# Peachy1-99-6-f.net
KiCad netlist of a schematic drawn in EAGLE
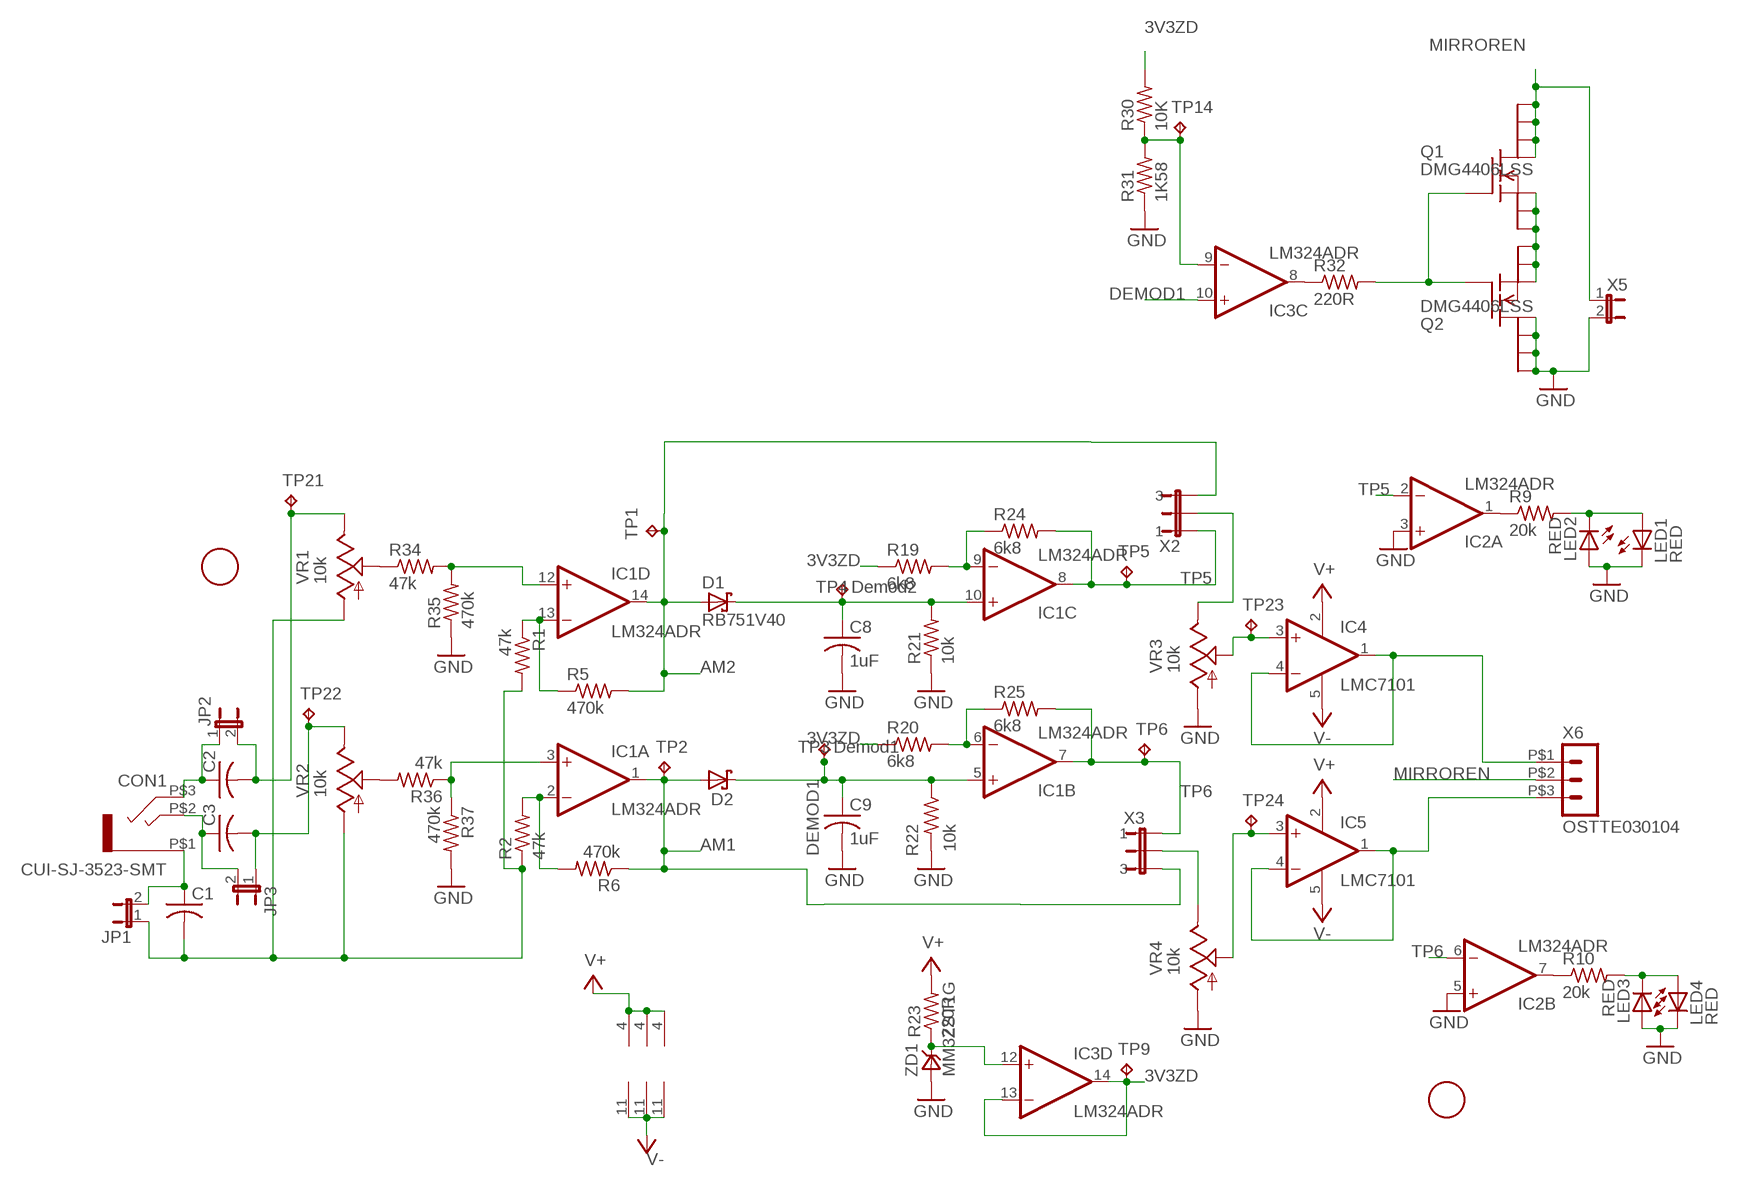
[diagram p0: schematic, sheet 1]
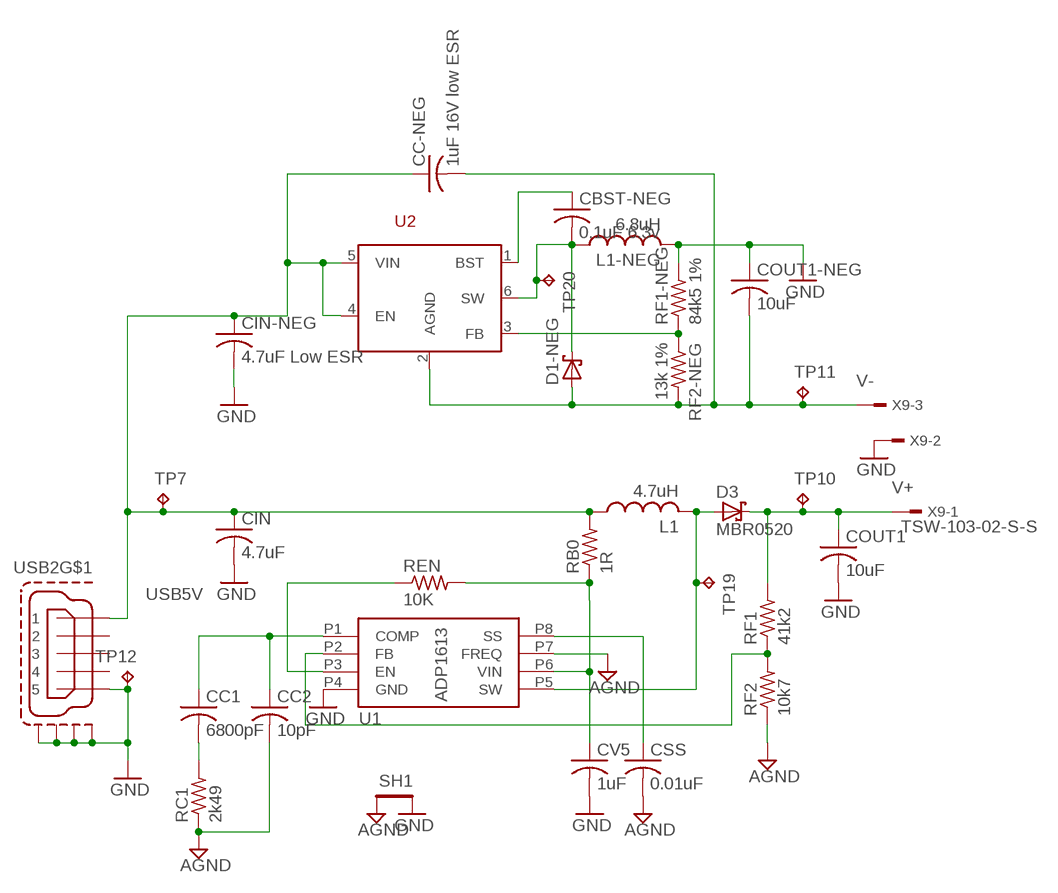
[diagram p1: schematic, sheet 2]
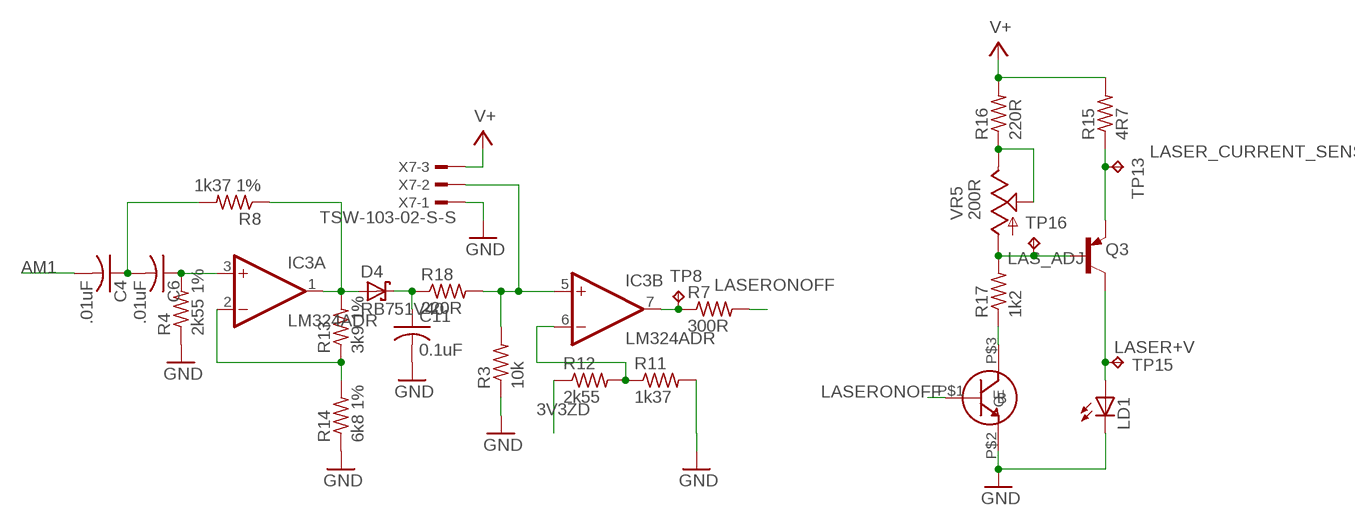
[diagram p2: schematic, sheet 3]
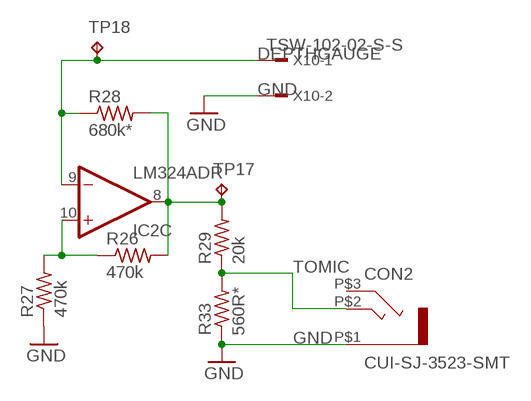
[diagram p3: schematic, sheet 4]

(export (version "E")
  (design (tool "Eeschema 10.0.6"))
  (components
    (comp (ref "CBST-NEG")
      (value "0.1uF 6.3v")
      (footprint "eagle-import:C0805")
      (fields (field (name "MPN") "CL21B104KACNNNC"))
      (libsource (lib "eagle-import") (part "C-US0805"))
    )
    (comp (ref "CC-NEG")
      (value "1uF 16V low ESR")
      (footprint "eagle-import:C0805")
      (fields (field (name "MPN") "CL21B105KBFNNNE"))
      (libsource (lib "eagle-import") (part "C-US0805"))
    )
    (comp (ref "CC1")
      (value "6800pF")
      (footprint "eagle-import:C0805")
      (fields (field (name "MPN") "CL21B682KBANNNC"))
      (libsource (lib "eagle-import") (part "C-US0805"))
    )
    (comp (ref "CC2")
      (value "10pF")
      (footprint "eagle-import:C0805")
      (fields (field (name "MPN") "CL21C100JCANNNC"))
      (libsource (lib "eagle-import") (part "C-US0805"))
    )
    (comp (ref "CIN")
      (value "4.7uF")
      (footprint "eagle-import:C0805")
      (fields (field (name "MPN") "CL21A475KOFNNNE"))
      (libsource (lib "eagle-import") (part "C-US0805"))
    )
    (comp (ref "CIN-NEG")
      (value "4.7uF Low ESR")
      (footprint "eagle-import:C0805")
      (fields (field (name "MPN") "CL21A475KOFNNNE"))
      (libsource (lib "eagle-import") (part "C-US0805"))
    )
    (comp (ref "COUT1")
      (value "10uF")
      (footprint "eagle-import:C0805")
      (fields (field (name "MPN") "CL21B106KQQNNNE"))
      (libsource (lib "eagle-import") (part "C-US0805"))
    )
    (comp (ref "COUT1-NEG")
      (value "10uF")
      (footprint "eagle-import:C0805")
      (fields (field (name "MPN") "CL21B106KQQNNNE"))
      (libsource (lib "eagle-import") (part "C-US0805"))
    )
    (comp (ref "CSS")
      (value "0.01uF")
      (footprint "eagle-import:C0805")
      (fields (field (name "MPN") "CL21B103KBANNNC"))
      (libsource (lib "eagle-import") (part "C-US0805"))
    )
    (comp (ref "CV5")
      (value "1uF")
      (footprint "eagle-import:C0805")
      (fields (field (name "MPN") "CL21B105KBFNNNE"))
      (libsource (lib "eagle-import") (part "C-US0805"))
    )
    (comp (ref "D1-NEG")
      (value "MBR0520LT1G")
      (footprint "eagle-import:SOD123")
      (fields (field (name "MPN") "MBR0520LT3G"))
      (libsource (lib "eagle-import") (part "SCHOTTKYSOD123"))
    )
    (comp (ref "D3")
      (value "MBR0520")
      (footprint "eagle-import:SOD123")
      (fields (field (name "MPN") "MBR0520LT3G"))
      (libsource (lib "eagle-import") (part "SCHOTTKYSOD123"))
    )
    (comp (ref "L1")
      (value "4.7uH")
      (footprint "eagle-import:L1210")
      (fields (field (name "MPN") "LQH32PN4R7NN0L"))
      (libsource (lib "eagle-import") (part "L-USL1210"))
    )
    (comp (ref "L1-NEG")
      (value "6.8uH")
      (footprint "eagle-import:L1210")
      (fields (field (name "MPN") "LQH32PN6R8NN0"))
      (libsource (lib "eagle-import") (part "L-USL1210"))
    )
    (comp (ref "RB0")
      (value "1R")
      (footprint "eagle-import:R0805")
      (fields (field (name "MPN") "RMCF0805JT1R00 "))
      (libsource (lib "eagle-import") (part "R-US_R0805"))
    )
    (comp (ref "RC1")
      (value "2k49")
      (footprint "eagle-import:R0805")
      (fields (field (name "MPN") "RMCF0805FT2K49"))
      (libsource (lib "eagle-import") (part "R-US_R0805"))
    )
    (comp (ref "REN")
      (value "10K")
      (footprint "eagle-import:R0805")
      (fields (field (name "MPN") "RMCF0805JT10K0"))
      (libsource (lib "eagle-import") (part "R-US_R0805"))
    )
    (comp (ref "RF1")
      (value "41k2")
      (footprint "eagle-import:R0805")
      (fields (field (name "MPN") "RC0805FR-0741K2L"))
      (libsource (lib "eagle-import") (part "R-US_R0805"))
    )
    (comp (ref "RF1-NEG")
      (value "84k5 1%")
      (footprint "eagle-import:R0805")
      (fields (field (name "MPN") "RC0805FR-0784K5L"))
      (libsource (lib "eagle-import") (part "R-US_R0805"))
    )
    (comp (ref "RF2")
      (value "10k7")
      (footprint "eagle-import:R0805")
      (fields (field (name "MPN") "RC2012F1072CS"))
      (libsource (lib "eagle-import") (part "R-US_R0805"))
    )
    (comp (ref "RF2-NEG")
      (value "13k 1%")
      (footprint "eagle-import:R0805")
      (fields (field (name "MPN") "RC0805FR-0713KL"))
      (libsource (lib "eagle-import") (part "R-US_R0805"))
    )
    (comp (ref "SH1")
      (value "SHORT-HT5")
      (footprint "eagle-import:SHORT_TOP-50")
      (libsource (lib "eagle-import") (part "SHORT-HT5"))
    )
    (comp (ref "TP7")
      (value "TP017HOLE")
      (footprint "eagle-import:TP017TH")
      (libsource (lib "eagle-import") (part "TP017HOLE"))
    )
    (comp (ref "TP10")
      (value "TP017HOLE")
      (footprint "eagle-import:TP017TH")
      (fields (field (name "TP_SIGNAL_NAME") "+V"))
      (libsource (lib "eagle-import") (part "TP017HOLE"))
    )
    (comp (ref "TP11")
      (value "TP017HOLE")
      (footprint "eagle-import:TP017TH")
      (fields (field (name "TP_SIGNAL_NAME") "V-"))
      (libsource (lib "eagle-import") (part "TP017HOLE"))
    )
    (comp (ref "TP12")
      (value "TP017HOLE")
      (footprint "eagle-import:TP017TH")
      (libsource (lib "eagle-import") (part "TP017HOLE"))
    )
    (comp (ref "TP19")
      (value "TP017HOLE")
      (footprint "eagle-import:TP017TH")
      (fields (field (name "TP_SIGNAL_NAME") "SW+"))
      (libsource (lib "eagle-import") (part "TP017HOLE"))
    )
    (comp (ref "TP20")
      (value "TP017HOLE")
      (footprint "eagle-import:TP017TH")
      (libsource (lib "eagle-import") (part "TP017HOLE"))
    )
    (comp (ref "U1")
      (value "ADP1613")
      (footprint "eagle-import:RM-8")
      (fields (field (name "MPN") "ADP1613ARMZ-R7"))
      (libsource (lib "eagle-import") (part "ADP1613"))
    )
    (comp (ref "U2")
      (value "ADP2300")
      (footprint "eagle-import:TSOT23-6")
      (fields (field (name "MPN") "ADP2300AUJZ-R7"))
      (libsource (lib "eagle-import") (part "ADP2300"))
    )
    (comp (ref "USB2")
      (value "FCI-MICROUSBAPCIRCUITS")
      (footprint "eagle-import:FCI-USB-10118193-APCIRCUITS")
      (fields (field (name "MPN") "10118193-0001LF"))
      (libsource (lib "eagle-import") (part "FCI-MICROUSBAPCIRCUITS"))
    )
    (comp (ref "X9")
      (value "TSW-103-02-S-S")
      (footprint "eagle-import:TSW-103-02-S-S")
      (fields (field (name "MPN") "TSW-103-07-T-S"))
      (libsource (lib "eagle-import") (part "TSW-103-02-S-S"))
    )
    (comp (ref "C4")
      (value ".01uF")
      (footprint "eagle-import:C0805")
      (fields (field (name "MPN") "CL21B103KBANNNC"))
      (libsource (lib "eagle-import") (part "C-US0805"))
    )
    (comp (ref "C6")
      (value ".01uF")
      (footprint "eagle-import:C0805")
      (fields (field (name "MPN") "CL21B103KBANNNC"))
      (libsource (lib "eagle-import") (part "C-US0805"))
    )
    (comp (ref "C11")
      (value "0.1uF")
      (footprint "eagle-import:C0805")
      (fields (field (name "MPN") "CL21B104KACNNNC"))
      (libsource (lib "eagle-import") (part "C-US0805"))
    )
    (comp (ref "D4")
      (value "RB751V40")
      (footprint "eagle-import:SOD323-R")
      (fields (field (name "MPN") "RB751V40,115"))
      (libsource (lib "eagle-import") (part "RB751V40"))
    )
    (comp (ref "IC3")
      (value "LM324ADR")
      (footprint "eagle-import:SOIC14(TI-PKG-D)")
      (fields (field (name "MPN") "LM324ADR"))
      (libsource (lib "eagle-import") (part "LM324ADR"))
    )
    (comp (ref "LD1")
      (value "LASERDIODELD2")
      (footprint "eagle-import:LASERDIODE2")
      (fields (field (name "MPN") "3 x (0552-2-15-15-11-27-10-0)"))
      (libsource (lib "eagle-import") (part "LASERDIODELD2"))
    )
    (comp (ref "Q3")
      (value "BC857CT")
      (footprint "eagle-import:SC-75")
      (fields (field (name "MPN") "BC857CT,115"))
      (libsource (lib "eagle-import") (part "BC857CT"))
    )
    (comp (ref "Q4")
      (value "MMBT3904")
      (footprint "eagle-import:SOT23")
      (fields (field (name "MPN") "MMBT3904,215"))
      (libsource (lib "eagle-import") (part "MMBT3904"))
    )
    (comp (ref "R3")
      (value "10k")
      (footprint "eagle-import:R0805")
      (fields (field (name "MPN") "RMCF0805JT10K0"))
      (libsource (lib "eagle-import") (part "R-US_R0805"))
    )
    (comp (ref "R4")
      (value "2k55 1%")
      (footprint "eagle-import:R0805")
      (fields (field (name "MPN") "RC0805FR-072K55L"))
      (libsource (lib "eagle-import") (part "R-US_R0805"))
    )
    (comp (ref "R7")
      (value "300R")
      (footprint "eagle-import:R0805")
      (fields (field (name "MPN") "RC0805JR-07300RL"))
      (libsource (lib "eagle-import") (part "R-US_R0805"))
    )
    (comp (ref "R8")
      (value "1k37 1%")
      (footprint "eagle-import:R0805")
      (fields (field (name "MPN") "RC0805FR-071K37L"))
      (libsource (lib "eagle-import") (part "R-US_R0805"))
    )
    (comp (ref "R11")
      (value "1k37")
      (footprint "eagle-import:R0805")
      (fields (field (name "MPN") "RC0805FR-071K37L"))
      (libsource (lib "eagle-import") (part "R-US_R0805"))
    )
    (comp (ref "R12")
      (value "2k55")
      (footprint "eagle-import:R0805")
      (fields (field (name "MPN") "RC0805FR-072K55L"))
      (libsource (lib "eagle-import") (part "R-US_R0805"))
    )
    (comp (ref "R13")
      (value "3k9 1%")
      (footprint "eagle-import:R0805")
      (fields (field (name "MPN") "RC0805FR-073K9L"))
      (libsource (lib "eagle-import") (part "R-US_R0805"))
    )
    (comp (ref "R14")
      (value "6k8 1%")
      (footprint "eagle-import:R0805")
      (fields (field (name "MPN") "RC0805FR-076K8L"))
      (libsource (lib "eagle-import") (part "R-US_R0805"))
    )
    (comp (ref "R15")
      (value "4R7")
      (footprint "eagle-import:R0805")
      (fields (field (name "MPN") "RMCF0805JT4R70"))
      (libsource (lib "eagle-import") (part "R-US_R0805"))
    )
    (comp (ref "R16")
      (value "220R")
      (footprint "eagle-import:R0805")
      (fields (field (name "MPN") "RC0805JR-07220RL"))
      (libsource (lib "eagle-import") (part "R-US_R0805"))
    )
    (comp (ref "R17")
      (value "1k2")
      (footprint "eagle-import:R0805")
      (fields (field (name "MPN") "RC2012J122CS"))
      (libsource (lib "eagle-import") (part "R-US_R0805"))
    )
    (comp (ref "R18")
      (value "220R")
      (footprint "eagle-import:R0805")
      (fields (field (name "MPN") "RMCF0805JT220R"))
      (libsource (lib "eagle-import") (part "R-US_R0805"))
    )
    (comp (ref "TP8")
      (value "TP017HOLE")
      (footprint "eagle-import:TP017TH")
      (libsource (lib "eagle-import") (part "TP017HOLE"))
    )
    (comp (ref "TP13")
      (value "TP017HOLE")
      (footprint "eagle-import:TP017TH")
      (fields (field (name "TP_SIGNAL_NAME") "LASER_CURRENT_SENSE"))
      (libsource (lib "eagle-import") (part "TP017HOLE"))
    )
    (comp (ref "TP15")
      (value "TP017HOLE")
      (footprint "eagle-import:TP017TH")
      (fields (field (name "TP_SIGNAL_NAME") "LASER+V"))
      (libsource (lib "eagle-import") (part "TP017HOLE"))
    )
    (comp (ref "TP16")
      (value "TP017HOLE")
      (footprint "eagle-import:TP017TH")
      (fields (field (name "TP_SIGNAL_NAME") "LAS_ADJ"))
      (libsource (lib "eagle-import") (part "TP017HOLE"))
    )
    (comp (ref "VR5")
      (value "200R")
      (footprint "eagle-import:TC33X")
      (fields (field (name "MPN") "???"))
      (libsource (lib "eagle-import") (part "TRIM_US-TC33X"))
    )
    (comp (ref "X7")
      (value "TSW-103-02-S-S")
      (footprint "eagle-import:TSW-103-02-S-S")
      (fields (field (name "MPN") "TSW-103-07-T-S"))
      (libsource (lib "eagle-import") (part "TSW-103-02-S-S"))
    )
    (comp (ref "C1")
      (value "C-US0805")
      (footprint "eagle-import:C0805")
      (libsource (lib "eagle-import") (part "C-US0805"))
    )
    (comp (ref "C2")
      (value "C-US0805")
      (footprint "eagle-import:C0805")
      (libsource (lib "eagle-import") (part "C-US0805"))
    )
    (comp (ref "C3")
      (value "C-US0805")
      (footprint "eagle-import:C0805")
      (libsource (lib "eagle-import") (part "C-US0805"))
    )
    (comp (ref "C8")
      (value "1uF")
      (footprint "eagle-import:C0805")
      (fields (field (name "MPN") "CL21B105KBFNNNE"))
      (libsource (lib "eagle-import") (part "C-US0805"))
    )
    (comp (ref "C9")
      (value "1uF")
      (footprint "eagle-import:C0805")
      (fields (field (name "MPN") "CL21B105KBFNNNE"))
      (libsource (lib "eagle-import") (part "C-US0805"))
    )
    (comp (ref "CON1")
      (value "CUI-SJ-3523-SMT")
      (footprint "eagle-import:CUI-SJ-3523-SMT")
      (fields (field (name "MPN") "SJ-3523-SMT-TR"))
      (libsource (lib "eagle-import") (part "CUI-SJ-3523-SMT"))
    )
    (comp (ref "D1")
      (value "RB751V40")
      (footprint "eagle-import:SOD323-R")
      (fields (field (name "MPN") "RB751V40,115"))
      (libsource (lib "eagle-import") (part "RB751V40"))
    )
    (comp (ref "D2")
      (value "RB751V40")
      (footprint "eagle-import:SOD323-R")
      (fields (field (name "MPN") "RB751V40,115"))
      (libsource (lib "eagle-import") (part "RB751V40"))
    )
    (comp (ref "IC1")
      (value "LM324ADR")
      (footprint "eagle-import:SOIC14(TI-PKG-D)")
      (fields (field (name "MPN") "LM324ADR"))
      (libsource (lib "eagle-import") (part "LM324ADR"))
    )
    (comp (ref "IC2")
      (value "LM324ADR")
      (footprint "eagle-import:SOIC14(TI-PKG-D)")
      (fields (field (name "MPN") "LM324ADR"))
      (libsource (lib "eagle-import") (part "LM324ADR"))
    )
    (comp (ref "IC4")
      (value "LMC7101")
      (footprint "eagle-import:SOT23-5")
      (fields (field (name "MPN") "LMC7101BYM5"))
      (libsource (lib "eagle-import") (part "LMC7101"))
    )
    (comp (ref "IC5")
      (value "LMC7101")
      (footprint "eagle-import:SOT23-5")
      (fields (field (name "MPN") "LMC7101BYM5"))
      (libsource (lib "eagle-import") (part "LMC7101"))
    )
    (comp (ref "JP1")
      (value "JUMPER-2SMD-NC")
      (footprint "eagle-import:SJ_2S")
      (libsource (lib "eagle-import") (part "JUMPER-2SMD-NC"))
    )
    (comp (ref "JP2")
      (value "JUMPER-2SMD-NC")
      (footprint "eagle-import:SJ_2S")
      (libsource (lib "eagle-import") (part "JUMPER-2SMD-NC"))
    )
    (comp (ref "JP3")
      (value "JUMPER-2SMD-NC")
      (footprint "eagle-import:SJ_2S")
      (libsource (lib "eagle-import") (part "JUMPER-2SMD-NC"))
    )
    (comp (ref "LED1")
      (value "RED")
      (footprint "eagle-import:CHIPLED_0603")
      (fields (field (name "MPN") "LS L29K-G1J2-1-Z"))
      (libsource (lib "eagle-import") (part "LEDCHIPLED_0603"))
    )
    (comp (ref "LED2")
      (value "RED")
      (footprint "eagle-import:CHIPLED_0603")
      (fields (field (name "MPN") "LS L29K-G1J2-1-Z"))
      (libsource (lib "eagle-import") (part "LEDCHIPLED_0603"))
    )
    (comp (ref "LED3")
      (value "RED")
      (footprint "eagle-import:CHIPLED_0603")
      (fields (field (name "MPN") "LS L29K-G1J2-1-Z"))
      (libsource (lib "eagle-import") (part "LEDCHIPLED_0603"))
    )
    (comp (ref "LED4")
      (value "RED")
      (footprint "eagle-import:CHIPLED_0603")
      (fields (field (name "MPN") "LS L29K-G1J2-1-Z"))
      (libsource (lib "eagle-import") (part "LEDCHIPLED_0603"))
    )
    (comp (ref "Q1")
      (value "DMG4406LSS")
      (footprint "eagle-import:SO8_DMG")
      (fields (field (name "MPN") "DMG4406LSS-13"))
      (libsource (lib "eagle-import") (part "DMG4406LSS"))
    )
    (comp (ref "Q2")
      (value "DMG4406LSS")
      (footprint "eagle-import:SO8_DMG")
      (fields (field (name "MPN") "DMG4406LSS-13"))
      (libsource (lib "eagle-import") (part "DMG4406LSS"))
    )
    (comp (ref "R1")
      (value "47k")
      (footprint "eagle-import:R0805")
      (fields (field (name "MPN") "RMCF0805JT47K0"))
      (libsource (lib "eagle-import") (part "R-US_R0805"))
    )
    (comp (ref "R2")
      (value "47k")
      (footprint "eagle-import:R0805")
      (fields (field (name "MPN") "RMCF0805JT47K0"))
      (libsource (lib "eagle-import") (part "R-US_R0805"))
    )
    (comp (ref "R5")
      (value "470k")
      (footprint "eagle-import:R0805")
      (fields (field (name "MPN") "RMCF0805JT470K"))
      (libsource (lib "eagle-import") (part "R-US_R0805"))
    )
    (comp (ref "R6")
      (value "470k")
      (footprint "eagle-import:R0805")
      (fields (field (name "MPN") "RMCF0805JT470K"))
      (libsource (lib "eagle-import") (part "R-US_R0805"))
    )
    (comp (ref "R9")
      (value "20k")
      (footprint "eagle-import:R0805")
      (fields (field (name "MPN") "RMCF0805JT20K0"))
      (libsource (lib "eagle-import") (part "R-US_R0805"))
    )
    (comp (ref "R10")
      (value "20k")
      (footprint "eagle-import:R0805")
      (fields (field (name "MPN") "RMCF0805JT20K0"))
      (libsource (lib "eagle-import") (part "R-US_R0805"))
    )
    (comp (ref "R19")
      (value "6k8")
      (footprint "eagle-import:R0805")
      (fields (field (name "MPN") "RC0805FR-076K8L"))
      (libsource (lib "eagle-import") (part "R-US_R0805"))
    )
    (comp (ref "R20")
      (value "6k8")
      (footprint "eagle-import:R0805")
      (fields (field (name "MPN") "RC0805FR-076K8L"))
      (libsource (lib "eagle-import") (part "R-US_R0805"))
    )
    (comp (ref "R21")
      (value "10k")
      (footprint "eagle-import:R0805")
      (fields (field (name "MPN") "RMCF0805JT10K0"))
      (libsource (lib "eagle-import") (part "R-US_R0805"))
    )
    (comp (ref "R22")
      (value "10k")
      (footprint "eagle-import:R0805")
      (fields (field (name "MPN") "RMCF0805JT10K0"))
      (libsource (lib "eagle-import") (part "R-US_R0805"))
    )
    (comp (ref "R23")
      (value "220R")
      (footprint "eagle-import:R0805")
      (fields (field (name "MPN") "RMCF0805JT220R"))
      (libsource (lib "eagle-import") (part "R-US_R0805"))
    )
    (comp (ref "R24")
      (value "6k8")
      (footprint "eagle-import:R0805")
      (fields (field (name "MPN") "RC0805FR-076K8L"))
      (libsource (lib "eagle-import") (part "R-US_R0805"))
    )
    (comp (ref "R25")
      (value "6k8")
      (footprint "eagle-import:R0805")
      (fields (field (name "MPN") "RC0805FR-076K8L"))
      (libsource (lib "eagle-import") (part "R-US_R0805"))
    )
    (comp (ref "R30")
      (value "10K")
      (footprint "eagle-import:R0805")
      (fields (field (name "MPN") "RMCF0805JT10K0"))
      (libsource (lib "eagle-import") (part "R-US_R0805"))
    )
    (comp (ref "R31")
      (value "1K58")
      (footprint "eagle-import:R0805")
      (fields (field (name "MPN") "RC0805FR-071K58L"))
      (libsource (lib "eagle-import") (part "R-US_R0805"))
    )
    (comp (ref "R32")
      (value "220R")
      (footprint "eagle-import:R0805")
      (fields (field (name "MPN") "RMCF0805JT220R"))
      (libsource (lib "eagle-import") (part "R-US_R0805"))
    )
    (comp (ref "R34")
      (value "47k")
      (footprint "eagle-import:R0805")
      (fields (field (name "MPN") "RMCF0805JT47K0"))
      (libsource (lib "eagle-import") (part "R-US_R0805"))
    )
    (comp (ref "R35")
      (value "470k")
      (footprint "eagle-import:R0805")
      (fields (field (name "MPN") "RMCF0805JT470K"))
      (libsource (lib "eagle-import") (part "R-US_R0805"))
    )
    (comp (ref "R36")
      (value "47k")
      (footprint "eagle-import:R0805")
      (fields (field (name "MPN") "RMCF0805JT47K0"))
      (libsource (lib "eagle-import") (part "R-US_R0805"))
    )
    (comp (ref "R37")
      (value "470k")
      (footprint "eagle-import:R0805")
      (fields (field (name "MPN") "RMCF0805JT470K"))
      (libsource (lib "eagle-import") (part "R-US_R0805"))
    )
    (comp (ref "TP1")
      (value "TP017HOLE")
      (footprint "eagle-import:TP017TH")
      (fields (field (name "TP_SIGNAL_NAME") "Preamp2"))
      (libsource (lib "eagle-import") (part "TP017HOLE"))
    )
    (comp (ref "TP2")
      (value "TP017HOLE")
      (footprint "eagle-import:TP017TH")
      (fields (field (name "TP_SIGNAL_NAME") "Preamp1"))
      (libsource (lib "eagle-import") (part "TP017HOLE"))
    )
    (comp (ref "TP3")
      (value "TP017HOLE")
      (footprint "eagle-import:TP017TH")
      (fields (field (name "TP_SIGNAL_NAME") "Demod1"))
      (libsource (lib "eagle-import") (part "TP017HOLE"))
    )
    (comp (ref "TP4")
      (value "TP017HOLE")
      (footprint "eagle-import:TP017TH")
      (fields (field (name "TP_SIGNAL_NAME") "Demod2"))
      (libsource (lib "eagle-import") (part "TP017HOLE"))
    )
    (comp (ref "TP5")
      (value "TP017HOLE")
      (footprint "eagle-import:TP017TH")
      (fields (field (name "TP_SIGNAL_NAME") "TP5"))
      (libsource (lib "eagle-import") (part "TP017HOLE"))
    )
    (comp (ref "TP6")
      (value "TP017HOLE")
      (footprint "eagle-import:TP017TH")
      (fields (field (name "TP_SIGNAL_NAME") "TP6"))
      (libsource (lib "eagle-import") (part "TP017HOLE"))
    )
    (comp (ref "TP9")
      (value "TP017HOLE")
      (footprint "eagle-import:TP017TH")
      (libsource (lib "eagle-import") (part "TP017HOLE"))
    )
    (comp (ref "TP14")
      (value "TP017HOLE")
      (footprint "eagle-import:TP017TH")
      (libsource (lib "eagle-import") (part "TP017HOLE"))
    )
    (comp (ref "TP21")
      (value "TP017HOLE")
      (footprint "eagle-import:TP017TH")
      (libsource (lib "eagle-import") (part "TP017HOLE"))
    )
    (comp (ref "TP22")
      (value "TP017HOLE")
      (footprint "eagle-import:TP017TH")
      (libsource (lib "eagle-import") (part "TP017HOLE"))
    )
    (comp (ref "TP23")
      (value "TP017HOLE")
      (footprint "eagle-import:TP017TH")
      (libsource (lib "eagle-import") (part "TP017HOLE"))
    )
    (comp (ref "TP24")
      (value "TP017HOLE")
      (footprint "eagle-import:TP017TH")
      (libsource (lib "eagle-import") (part "TP017HOLE"))
    )
    (comp (ref "U$2")
      (value "FIDUCIAL")
      (footprint "eagle-import:FIDUCIAL_1MM")
      (libsource (lib "eagle-import") (part "FIDUCIAL"))
    )
    (comp (ref "U$3")
      (value "FIDUCIAL")
      (footprint "eagle-import:FIDUCIAL_1MM")
      (libsource (lib "eagle-import") (part "FIDUCIAL"))
    )
    (comp (ref "VR1")
      (value "10k")
      (footprint "eagle-import:67W")
      (fields (field (name "MPN") "67WR10KLF"))
      (libsource (lib "eagle-import") (part "TRIM_US-67W"))
    )
    (comp (ref "VR2")
      (value "10k")
      (footprint "eagle-import:67W")
      (fields (field (name "MPN") "67WR10KLF"))
      (libsource (lib "eagle-import") (part "TRIM_US-67W"))
    )
    (comp (ref "VR3")
      (value "10k")
      (footprint "eagle-import:PVZ3A")
      (fields (field (name "MPN") "PVZ3A103C01R00"))
      (libsource (lib "eagle-import") (part "TRIM_US-PVZ3A"))
    )
    (comp (ref "VR4")
      (value "10k")
      (footprint "eagle-import:PVZ3A")
      (fields (field (name "MPN") "PVZ3A103C01R00"))
      (libsource (lib "eagle-import") (part "TRIM_US-PVZ3A"))
    )
    (comp (ref "X2")
      (value "JUMPER-31-2")
      (footprint "eagle-import:SJ_3_PASTE1&2")
      (libsource (lib "eagle-import") (part "JUMPER-31-2"))
    )
    (comp (ref "X3")
      (value "JUMPER-31-2")
      (footprint "eagle-import:SJ_3_PASTE1&2")
      (libsource (lib "eagle-import") (part "JUMPER-31-2"))
    )
    (comp (ref "X5")
      (value "JUMPER-2SMD-NO")
      (footprint "eagle-import:SJ_2S-NO")
      (libsource (lib "eagle-import") (part "JUMPER-2SMD-NO"))
    )
    (comp (ref "X6")
      (value "OSTTE030104")
      (footprint "eagle-import:OSTTE030104")
      (libsource (lib "eagle-import") (part "OSTTE030104"))
    )
    (comp (ref "ZD1")
      (value "MM3ZST1G")
      (footprint "eagle-import:SOD323-R")
      (fields (field (name "MPN") "BZX384-B3V3,115"))
      (libsource (lib "eagle-import") (part "MM3ZST1G"))
    )
    (comp (ref "CON2")
      (value "CUI-SJ-3523-SMT")
      (footprint "eagle-import:CUI-SJ-3523-SMT")
      (fields (field (name "MPN") "SJ-3523-SMT-TR"))
      (libsource (lib "eagle-import") (part "CUI-SJ-3523-SMT"))
    )
    (comp (ref "R26")
      (value "470k")
      (footprint "eagle-import:R0805")
      (fields (field (name "MPN") "RMCF0805JT470K"))
      (libsource (lib "eagle-import") (part "R-US_R0805"))
    )
    (comp (ref "R27")
      (value "470k")
      (footprint "eagle-import:R0805")
      (fields (field (name "MPN") "RMCF0805JT470K"))
      (libsource (lib "eagle-import") (part "R-US_R0805"))
    )
    (comp (ref "R28")
      (value "680k*")
      (footprint "eagle-import:70543-02")
      (fields (field (name "MPN") "PPTC021LFBN-RC"))
      (libsource (lib "eagle-import") (part "R-US_SOCKET(.1)"))
    )
    (comp (ref "R29")
      (value "20k")
      (footprint "eagle-import:R0805")
      (fields (field (name "MPN") "RMCF0805JT20K0"))
      (libsource (lib "eagle-import") (part "R-US_R0805"))
    )
    (comp (ref "R33")
      (value "560R*")
      (footprint "eagle-import:R0805")
      (fields (field (name "MPN") "RMCF0805JT560R"))
      (libsource (lib "eagle-import") (part "R-US_R0805"))
    )
    (comp (ref "TP17")
      (value "TP017HOLE")
      (footprint "eagle-import:TP017TH")
      (libsource (lib "eagle-import") (part "TP017HOLE"))
    )
    (comp (ref "TP18")
      (value "TP017HOLE")
      (footprint "eagle-import:TP017TH")
      (libsource (lib "eagle-import") (part "TP017HOLE"))
    )
    (comp (ref "X10")
      (value "TSW-102-02-S-S")
      (footprint "eagle-import:TSW-102-02-S-S")
      (libsource (lib "eagle-import") (part "TSW-102-02-S-S"))
    )
  )
  (nets
    (net (code "1") (name "3V3ZD") (class "Default")
      (node (ref "IC3") (pin "13") (pinfunction "-IN_13") (pintype "input"))
      (node (ref "IC3") (pin "14") (pinfunction "OUT_14") (pintype "output"))
      (node (ref "R12") (pin "1") (pinfunction "1_1") (pintype "passive"))
      (node (ref "R19") (pin "1") (pinfunction "1_1") (pintype "passive"))
      (node (ref "R20") (pin "1") (pinfunction "1_1") (pintype "passive"))
      (node (ref "R30") (pin "2") (pinfunction "2_2") (pintype "passive"))
      (node (ref "TP9") (pin "P$1") (pinfunction "TP_P$1") (pintype "input"))
    )
    (net (code "2") (name "AGND") (class "Default")
      (node (ref "CC2") (pin "2") (pinfunction "2_2") (pintype "passive"))
      (node (ref "CSS") (pin "2") (pinfunction "2_2") (pintype "passive"))
      (node (ref "RC1") (pin "1") (pinfunction "1_1") (pintype "passive"))
      (node (ref "RF2") (pin "1") (pinfunction "1_1") (pintype "passive"))
      (node (ref "SH1") (pin "1") (pinfunction "P$1_1") (pintype "bidirectional"))
      (node (ref "U1") (pin "P7") (pinfunction "FREQ_P7") (pintype "bidirectional"))
    )
    (net (code "3") (name "AM1") (class "Default")
      (node (ref "C4") (pin "2") (pinfunction "2_2") (pintype "passive"))
      (node (ref "D2") (pin "A") (pinfunction "A_A") (pintype "passive"))
      (node (ref "IC1") (pin "1") (pinfunction "OUT_1") (pintype "output"))
      (node (ref "R6") (pin "1") (pinfunction "1_1") (pintype "passive"))
      (node (ref "TP2") (pin "P$1") (pinfunction "TP_P$1") (pintype "input"))
      (node (ref "X3") (pin "3") (pinfunction "3_3") (pintype "passive"))
    )
    (net (code "4") (name "AM2") (class "Default")
      (node (ref "D1") (pin "A") (pinfunction "A_A") (pintype "passive"))
      (node (ref "IC1") (pin "14") (pinfunction "OUT_14") (pintype "output"))
      (node (ref "R5") (pin "2") (pinfunction "2_2") (pintype "passive"))
      (node (ref "TP1") (pin "P$1") (pinfunction "TP_P$1") (pintype "input"))
      (node (ref "X2") (pin "3") (pinfunction "3_3") (pintype "passive"))
    )
    (net (code "5") (name "DEMOD1") (class "Default")
      (node (ref "C9") (pin "1") (pinfunction "1_1") (pintype "passive"))
      (node (ref "D2") (pin "C") (pinfunction "C_C") (pintype "passive"))
      (node (ref "IC1") (pin "5") (pinfunction "+IN_5") (pintype "input"))
      (node (ref "IC3") (pin "10") (pinfunction "+IN_10") (pintype "input"))
      (node (ref "R22") (pin "1") (pinfunction "1_1") (pintype "passive"))
      (node (ref "TP3") (pin "P$1") (pinfunction "TP_P$1") (pintype "input"))
    )
    (net (code "6") (name "DEPTHGAUGE") (class "Default")
      (node (ref "IC2") (pin "9") (pinfunction "-IN_9") (pintype "input"))
      (node (ref "R28") (pin "1") (pinfunction "1_1") (pintype "passive"))
      (node (ref "TP18") (pin "P$1") (pinfunction "TP_P$1") (pintype "input"))
      (node (ref "X10") (pin "1") (pinfunction "1_1") (pintype "passive"))
    )
    (net (code "7") (name "GND") (class "Default")
      (node (ref "C11") (pin "2") (pinfunction "2_2") (pintype "passive"))
      (node (ref "C8") (pin "2") (pinfunction "2_2") (pintype "passive"))
      (node (ref "C9") (pin "2") (pinfunction "2_2") (pintype "passive"))
      (node (ref "CIN") (pin "2") (pinfunction "2_2") (pintype "passive"))
      (node (ref "CIN-NEG") (pin "2") (pinfunction "2_2") (pintype "passive"))
      (node (ref "CON2") (pin "P$1") (pinfunction "1_P$1") (pintype "passive"))
      (node (ref "COUT1") (pin "2") (pinfunction "2_2") (pintype "passive"))
      (node (ref "COUT1-NEG") (pin "1") (pinfunction "1_1") (pintype "passive"))
      (node (ref "CV5") (pin "2") (pinfunction "2_2") (pintype "passive"))
      (node (ref "IC2") (pin "3") (pinfunction "+IN_3") (pintype "input"))
      (node (ref "IC2") (pin "5") (pinfunction "+IN_5") (pintype "input"))
      (node (ref "L1-NEG") (pin "2") (pinfunction "2_2") (pintype "passive"))
      (node (ref "LD1") (pin "P$3") (pinfunction "C_P$3") (pintype "passive"))
      (node (ref "LED1") (pin "C") (pinfunction "C_C") (pintype "passive"))
      (node (ref "LED2") (pin "A") (pinfunction "A_A") (pintype "passive"))
      (node (ref "LED3") (pin "A") (pinfunction "A_A") (pintype "passive"))
      (node (ref "LED4") (pin "C") (pinfunction "C_C") (pintype "passive"))
      (node (ref "Q2") (pin "P$5") (pinfunction "D_P$5") (pintype "passive"))
      (node (ref "Q2") (pin "P$6") (pinfunction "D_P$6") (pintype "passive"))
      (node (ref "Q2") (pin "P$7") (pinfunction "D_P$7") (pintype "passive"))
      (node (ref "Q2") (pin "P$8") (pinfunction "D_P$8") (pintype "passive"))
      (node (ref "Q4") (pin "P$2") (pinfunction "E_P$2") (pintype "input"))
      (node (ref "R11") (pin "2") (pinfunction "2_2") (pintype "passive"))
      (node (ref "R14") (pin "1") (pinfunction "1_1") (pintype "passive"))
      (node (ref "R21") (pin "1") (pinfunction "1_1") (pintype "passive"))
      (node (ref "R22") (pin "2") (pinfunction "2_2") (pintype "passive"))
      (node (ref "R27") (pin "1") (pinfunction "1_1") (pintype "passive"))
      (node (ref "R3") (pin "1") (pinfunction "1_1") (pintype "passive"))
      (node (ref "R31") (pin "1") (pinfunction "1_1") (pintype "passive"))
      (node (ref "R33") (pin "1") (pinfunction "1_1") (pintype "passive"))
      (node (ref "R35") (pin "1") (pinfunction "1_1") (pintype "passive"))
      (node (ref "R37") (pin "2") (pinfunction "2_2") (pintype "passive"))
      (node (ref "R4") (pin "1") (pinfunction "1_1") (pintype "passive"))
      (node (ref "RF1-NEG") (pin "2") (pinfunction "2_2") (pintype "passive"))
      (node (ref "SH1") (pin "2") (pinfunction "P$2_2") (pintype "bidirectional"))
      (node (ref "TP12") (pin "P$1") (pinfunction "TP_P$1") (pintype "input"))
      (node (ref "U1") (pin "P4") (pinfunction "GND_P4") (pintype "bidirectional"))
      (node (ref "USB2") (pin "P$11") (pinfunction "S4_P$11") (pintype "passive"))
      (node (ref "USB2") (pin "P$5") (pinfunction "5_P$5") (pintype "input"))
      (node (ref "USB2") (pin "P$6") (pinfunction "S1_P$6") (pintype "passive"))
      (node (ref "USB2") (pin "P$7") (pinfunction "S2_P$7") (pintype "passive"))
      (node (ref "USB2") (pin "P$8") (pinfunction "S3_P$8") (pintype "passive"))
      (node (ref "VR3") (pin "P$1") (pinfunction "A_P$1") (pintype "passive"))
      (node (ref "VR4") (pin "P$1") (pinfunction "A_P$1") (pintype "passive"))
      (node (ref "X10") (pin "2") (pinfunction "1_2") (pintype "passive"))
      (node (ref "X5") (pin "2") (pinfunction "2_2") (pintype "passive"))
      (node (ref "X7") (pin "1") (pinfunction "1_1") (pintype "passive"))
      (node (ref "X9") (pin "2") (pinfunction "1_2") (pintype "passive"))
      (node (ref "ZD1") (pin "A") (pinfunction "A_A") (pintype "passive"))
    )
    (net (code "8") (name "LASERONOFF") (class "Default")
      (node (ref "Q4") (pin "P$1") (pinfunction "B_P$1") (pintype "input"))
      (node (ref "R7") (pin "2") (pinfunction "2_2") (pintype "passive"))
    )
    (net (code "9") (name "MIRROREN") (class "Default")
      (node (ref "Q1") (pin "P$5") (pinfunction "D_P$5") (pintype "passive"))
      (node (ref "Q1") (pin "P$6") (pinfunction "D_P$6") (pintype "passive"))
      (node (ref "Q1") (pin "P$7") (pinfunction "D_P$7") (pintype "passive"))
      (node (ref "Q1") (pin "P$8") (pinfunction "D_P$8") (pintype "passive"))
      (node (ref "X5") (pin "1") (pinfunction "1_1") (pintype "passive"))
      (node (ref "X6") (pin "P$2") (pinfunction "2_P$2") (pintype "passive"))
    )
    (net (code "10") (name "Net-(C1-Pad2)") (class "Default")
      (node (ref "C1") (pin "2") (pinfunction "2_2") (pintype "passive"))
      (node (ref "JP1") (pin "1") (pinfunction "1_1") (pintype "passive"))
      (node (ref "R1") (pin "2") (pinfunction "2_2") (pintype "passive"))
      (node (ref "R2") (pin "1") (pinfunction "1_1") (pintype "passive"))
      (node (ref "VR1") (pin "A") (pinfunction "A_A") (pintype "passive"))
      (node (ref "VR2") (pin "A") (pinfunction "A_A") (pintype "passive"))
    )
    (net (code "11") (name "Net-(C4-Pad1)") (class "Default")
      (node (ref "C4") (pin "1") (pinfunction "1_1") (pintype "passive"))
      (node (ref "C6") (pin "2") (pinfunction "2_2") (pintype "passive"))
      (node (ref "R8") (pin "2") (pinfunction "2_2") (pintype "passive"))
    )
    (net (code "12") (name "Net-(C11-Pad1)") (class "Default")
      (node (ref "C11") (pin "1") (pinfunction "1_1") (pintype "passive"))
      (node (ref "D4") (pin "C") (pinfunction "C_C") (pintype "passive"))
      (node (ref "R18") (pin "1") (pinfunction "1_1") (pintype "passive"))
    )
    (net (code "13") (name "Net-(CC1-Pad2)") (class "Default")
      (node (ref "CC1") (pin "2") (pinfunction "2_2") (pintype "passive"))
      (node (ref "RC1") (pin "2") (pinfunction "2_2") (pintype "passive"))
    )
    (net (code "14") (name "Net-(CON1-1)") (class "Default")
      (node (ref "C1") (pin "1") (pinfunction "1_1") (pintype "passive"))
      (node (ref "CON1") (pin "P$1") (pinfunction "1_P$1") (pintype "passive"))
      (node (ref "JP1") (pin "2") (pinfunction "2_2") (pintype "passive"))
    )
    (net (code "15") (name "Net-(CON1-2)") (class "Default")
      (node (ref "C2") (pin "1") (pinfunction "1_1") (pintype "passive"))
      (node (ref "CON1") (pin "P$3") (pinfunction "2_P$3") (pintype "passive"))
      (node (ref "JP2") (pin "1") (pinfunction "1_1") (pintype "passive"))
    )
    (net (code "16") (name "Net-(CON1-3)") (class "Default")
      (node (ref "C3") (pin "1") (pinfunction "1_1") (pintype "passive"))
      (node (ref "CON1") (pin "P$2") (pinfunction "3_P$2") (pintype "passive"))
      (node (ref "JP3") (pin "2") (pinfunction "2_2") (pintype "passive"))
    )
    (net (code "17") (name "Net-(IC1A-+IN)") (class "Default")
      (node (ref "IC1") (pin "3") (pinfunction "+IN_3") (pintype "input"))
      (node (ref "R36") (pin "1") (pinfunction "1_1") (pintype "passive"))
      (node (ref "R37") (pin "1") (pinfunction "1_1") (pintype "passive"))
    )
    (net (code "18") (name "Net-(IC1A--IN)") (class "Default")
      (node (ref "IC1") (pin "2") (pinfunction "-IN_2") (pintype "input"))
      (node (ref "R2") (pin "2") (pinfunction "2_2") (pintype "passive"))
      (node (ref "R6") (pin "2") (pinfunction "2_2") (pintype "passive"))
    )
    (net (code "19") (name "Net-(IC1B--IN)") (class "Default")
      (node (ref "IC1") (pin "6") (pinfunction "-IN_6") (pintype "input"))
      (node (ref "R20") (pin "2") (pinfunction "2_2") (pintype "passive"))
      (node (ref "R25") (pin "1") (pinfunction "1_1") (pintype "passive"))
    )
    (net (code "20") (name "Net-(IC1C-+IN)") (class "Default")
      (node (ref "C8") (pin "1") (pinfunction "1_1") (pintype "passive"))
      (node (ref "D1") (pin "C") (pinfunction "C_C") (pintype "passive"))
      (node (ref "IC1") (pin "10") (pinfunction "+IN_10") (pintype "input"))
      (node (ref "R21") (pin "2") (pinfunction "2_2") (pintype "passive"))
      (node (ref "TP4") (pin "P$1") (pinfunction "TP_P$1") (pintype "input"))
    )
    (net (code "21") (name "Net-(IC1C--IN)") (class "Default")
      (node (ref "IC1") (pin "9") (pinfunction "-IN_9") (pintype "input"))
      (node (ref "R19") (pin "2") (pinfunction "2_2") (pintype "passive"))
      (node (ref "R24") (pin "1") (pinfunction "1_1") (pintype "passive"))
    )
    (net (code "22") (name "Net-(IC1D-+IN)") (class "Default")
      (node (ref "IC1") (pin "12") (pinfunction "+IN_12") (pintype "input"))
      (node (ref "R34") (pin "2") (pinfunction "2_2") (pintype "passive"))
      (node (ref "R35") (pin "2") (pinfunction "2_2") (pintype "passive"))
    )
    (net (code "23") (name "Net-(IC1D--IN)") (class "Default")
      (node (ref "IC1") (pin "13") (pinfunction "-IN_13") (pintype "input"))
      (node (ref "R1") (pin "1") (pinfunction "1_1") (pintype "passive"))
      (node (ref "R5") (pin "1") (pinfunction "1_1") (pintype "passive"))
    )
    (net (code "24") (name "Net-(IC2A-OUT)") (class "Default")
      (node (ref "IC2") (pin "1") (pinfunction "OUT_1") (pintype "output"))
      (node (ref "R9") (pin "1") (pinfunction "1_1") (pintype "passive"))
    )
    (net (code "25") (name "Net-(IC2B-OUT)") (class "Default")
      (node (ref "IC2") (pin "7") (pinfunction "OUT_7") (pintype "output"))
      (node (ref "R10") (pin "1") (pinfunction "1_1") (pintype "passive"))
    )
    (net (code "26") (name "Net-(IC2C-+IN)") (class "Default")
      (node (ref "IC2") (pin "10") (pinfunction "+IN_10") (pintype "input"))
      (node (ref "R26") (pin "1") (pinfunction "1_1") (pintype "passive"))
      (node (ref "R27") (pin "2") (pinfunction "2_2") (pintype "passive"))
    )
    (net (code "27") (name "Net-(IC2C-OUT)") (class "Default")
      (node (ref "IC2") (pin "8") (pinfunction "OUT_8") (pintype "output"))
      (node (ref "R26") (pin "2") (pinfunction "2_2") (pintype "passive"))
      (node (ref "R28") (pin "2") (pinfunction "2_2") (pintype "passive"))
      (node (ref "R29") (pin "2") (pinfunction "2_2") (pintype "passive"))
      (node (ref "TP17") (pin "P$1") (pinfunction "TP_P$1") (pintype "input"))
    )
    (net (code "28") (name "Net-(IC3A-+IN)") (class "Default")
      (node (ref "C6") (pin "1") (pinfunction "1_1") (pintype "passive"))
      (node (ref "IC3") (pin "3") (pinfunction "+IN_3") (pintype "input"))
      (node (ref "R4") (pin "2") (pinfunction "2_2") (pintype "passive"))
    )
    (net (code "29") (name "Net-(IC3A--IN)") (class "Default")
      (node (ref "IC3") (pin "2") (pinfunction "-IN_2") (pintype "input"))
      (node (ref "R13") (pin "1") (pinfunction "1_1") (pintype "passive"))
      (node (ref "R14") (pin "2") (pinfunction "2_2") (pintype "passive"))
    )
    (net (code "30") (name "Net-(IC3A-OUT)") (class "Default")
      (node (ref "D4") (pin "A") (pinfunction "A_A") (pintype "passive"))
      (node (ref "IC3") (pin "1") (pinfunction "OUT_1") (pintype "output"))
      (node (ref "R13") (pin "2") (pinfunction "2_2") (pintype "passive"))
      (node (ref "R8") (pin "1") (pinfunction "1_1") (pintype "passive"))
    )
    (net (code "31") (name "Net-(IC3B-+IN)") (class "Default")
      (node (ref "IC3") (pin "5") (pinfunction "+IN_5") (pintype "input"))
      (node (ref "R18") (pin "2") (pinfunction "2_2") (pintype "passive"))
      (node (ref "R3") (pin "2") (pinfunction "2_2") (pintype "passive"))
      (node (ref "X7") (pin "2") (pinfunction "1_2") (pintype "passive"))
    )
    (net (code "32") (name "Net-(IC3B--IN)") (class "Default")
      (node (ref "IC3") (pin "6") (pinfunction "-IN_6") (pintype "input"))
      (node (ref "R11") (pin "1") (pinfunction "1_1") (pintype "passive"))
      (node (ref "R12") (pin "2") (pinfunction "2_2") (pintype "passive"))
    )
    (net (code "33") (name "Net-(IC3B-OUT)") (class "Default")
      (node (ref "IC3") (pin "7") (pinfunction "OUT_7") (pintype "output"))
      (node (ref "R7") (pin "1") (pinfunction "1_1") (pintype "passive"))
      (node (ref "TP8") (pin "P$1") (pinfunction "TP_P$1") (pintype "input"))
    )
    (net (code "34") (name "Net-(IC3C--IN)") (class "Default")
      (node (ref "IC3") (pin "9") (pinfunction "-IN_9") (pintype "input"))
      (node (ref "R30") (pin "1") (pinfunction "1_1") (pintype "passive"))
      (node (ref "R31") (pin "2") (pinfunction "2_2") (pintype "passive"))
      (node (ref "TP14") (pin "P$1") (pinfunction "TP_P$1") (pintype "input"))
    )
    (net (code "35") (name "Net-(IC3C-OUT)") (class "Default")
      (node (ref "IC3") (pin "8") (pinfunction "OUT_8") (pintype "output"))
      (node (ref "R32") (pin "1") (pinfunction "1_1") (pintype "passive"))
    )
    (net (code "36") (name "Net-(IC3D-+IN)") (class "Default")
      (node (ref "IC3") (pin "12") (pinfunction "+IN_12") (pintype "input"))
      (node (ref "R23") (pin "1") (pinfunction "1_1") (pintype "passive"))
      (node (ref "ZD1") (pin "C") (pinfunction "C_C") (pintype "passive"))
    )
    (net (code "37") (name "Net-(IC4-+IN)") (class "Default")
      (node (ref "IC4") (pin "3") (pinfunction "+IN_3") (pintype "input"))
      (node (ref "TP23") (pin "P$1") (pinfunction "TP_P$1") (pintype "input"))
      (node (ref "VR3") (pin "P$2") (pinfunction "S_P$2") (pintype "passive"))
    )
    (net (code "38") (name "Net-(IC4--IN)") (class "Default")
      (node (ref "IC4") (pin "1") (pinfunction "OUT_1") (pintype "output"))
      (node (ref "IC4") (pin "4") (pinfunction "-IN_4") (pintype "input"))
      (node (ref "X6") (pin "P$1") (pinfunction "1_P$1") (pintype "passive"))
    )
    (net (code "39") (name "Net-(IC5-+IN)") (class "Default")
      (node (ref "IC5") (pin "3") (pinfunction "+IN_3") (pintype "input"))
      (node (ref "TP24") (pin "P$1") (pinfunction "TP_P$1") (pintype "input"))
      (node (ref "VR4") (pin "P$2") (pinfunction "S_P$2") (pintype "passive"))
    )
    (net (code "40") (name "Net-(IC5--IN)") (class "Default")
      (node (ref "IC5") (pin "1") (pinfunction "OUT_1") (pintype "output"))
      (node (ref "IC5") (pin "4") (pinfunction "-IN_4") (pintype "input"))
      (node (ref "X6") (pin "P$3") (pinfunction "3_P$3") (pintype "passive"))
    )
    (net (code "41") (name "Net-(LD1-A)") (class "Default")
      (node (ref "LD1") (pin "P$1") (pinfunction "A_P$1") (pintype "passive"))
      (node (ref "Q3") (pin "P$3") (pinfunction "C_P$3") (pintype "passive"))
      (node (ref "TP15") (pin "P$1") (pinfunction "TP_P$1") (pintype "input"))
    )
    (net (code "42") (name "Net-(LED1-PadA)") (class "Default")
      (node (ref "LED1") (pin "A") (pinfunction "A_A") (pintype "passive"))
      (node (ref "LED2") (pin "C") (pinfunction "C_C") (pintype "passive"))
      (node (ref "R9") (pin "2") (pinfunction "2_2") (pintype "passive"))
    )
    (net (code "43") (name "Net-(LED3-PadC)") (class "Default")
      (node (ref "LED3") (pin "C") (pinfunction "C_C") (pintype "passive"))
      (node (ref "LED4") (pin "A") (pinfunction "A_A") (pintype "passive"))
      (node (ref "R10") (pin "2") (pinfunction "2_2") (pintype "passive"))
    )
    (net (code "44") (name "Net-(Q1-G)") (class "Default")
      (node (ref "Q1") (pin "P$4") (pinfunction "G_P$4") (pintype "passive"))
      (node (ref "Q2") (pin "P$4") (pinfunction "G_P$4") (pintype "passive"))
      (node (ref "R32") (pin "2") (pinfunction "2_2") (pintype "passive"))
    )
    (net (code "45") (name "Net-(Q1-S-PadP$1)") (class "Default")
      (node (ref "Q1") (pin "P$1") (pinfunction "S_P$1") (pintype "passive"))
      (node (ref "Q1") (pin "P$2") (pinfunction "S_P$2") (pintype "passive"))
      (node (ref "Q1") (pin "P$3") (pinfunction "S_P$3") (pintype "passive"))
      (node (ref "Q2") (pin "P$1") (pinfunction "S_P$1") (pintype "passive"))
      (node (ref "Q2") (pin "P$2") (pinfunction "S_P$2") (pintype "passive"))
      (node (ref "Q2") (pin "P$3") (pinfunction "S_P$3") (pintype "passive"))
    )
    (net (code "46") (name "Net-(Q3-B)") (class "Default")
      (node (ref "Q3") (pin "P$1") (pinfunction "B_P$1") (pintype "passive"))
      (node (ref "R17") (pin "2") (pinfunction "2_2") (pintype "passive"))
      (node (ref "TP16") (pin "P$1") (pinfunction "TP_P$1") (pintype "input"))
      (node (ref "VR5") (pin "P$1") (pinfunction "A_P$1") (pintype "passive"))
    )
    (net (code "47") (name "Net-(Q3-E)") (class "Default")
      (node (ref "Q3") (pin "P$2") (pinfunction "E_P$2") (pintype "passive"))
      (node (ref "R15") (pin "1") (pinfunction "1_1") (pintype "passive"))
      (node (ref "TP13") (pin "P$1") (pinfunction "TP_P$1") (pintype "input"))
    )
    (net (code "48") (name "Net-(Q4-C)") (class "Default")
      (node (ref "Q4") (pin "P$3") (pinfunction "C_P$3") (pintype "input"))
      (node (ref "R17") (pin "1") (pinfunction "1_1") (pintype "passive"))
    )
    (net (code "49") (name "Net-(R34-Pad1)") (class "Default")
      (node (ref "R34") (pin "1") (pinfunction "1_1") (pintype "passive"))
      (node (ref "VR1") (pin "S") (pinfunction "S_S") (pintype "passive"))
    )
    (net (code "50") (name "Net-(R36-Pad2)") (class "Default")
      (node (ref "R36") (pin "2") (pinfunction "2_2") (pintype "passive"))
      (node (ref "VR2") (pin "S") (pinfunction "S_S") (pintype "passive"))
    )
    (net (code "51") (name "Net-(TP19-TP)") (class "Default")
      (node (ref "D3") (pin "A") (pinfunction "A_A") (pintype "passive"))
      (node (ref "L1") (pin "2") (pinfunction "2_2") (pintype "passive"))
      (node (ref "TP19") (pin "P$1") (pinfunction "TP_P$1") (pintype "input"))
      (node (ref "U1") (pin "P5") (pinfunction "SW_P5") (pintype "bidirectional"))
    )
    (net (code "52") (name "Net-(TP20-TP)") (class "Default")
      (node (ref "CBST-NEG") (pin "2") (pinfunction "2_2") (pintype "passive"))
      (node (ref "D1-NEG") (pin "C") (pinfunction "C_C") (pintype "passive"))
      (node (ref "L1-NEG") (pin "1") (pinfunction "1_1") (pintype "passive"))
      (node (ref "TP20") (pin "P$1") (pinfunction "TP_P$1") (pintype "input"))
      (node (ref "U2") (pin "6") (pinfunction "SW_6") (pintype "bidirectional"))
    )
    (net (code "53") (name "Net-(TP21-TP)") (class "Default")
      (node (ref "C2") (pin "2") (pinfunction "2_2") (pintype "passive"))
      (node (ref "JP2") (pin "2") (pinfunction "2_2") (pintype "passive"))
      (node (ref "TP21") (pin "P$1") (pinfunction "TP_P$1") (pintype "input"))
      (node (ref "VR1") (pin "E") (pinfunction "E_E") (pintype "passive"))
    )
    (net (code "54") (name "Net-(TP22-TP)") (class "Default")
      (node (ref "C3") (pin "2") (pinfunction "2_2") (pintype "passive"))
      (node (ref "JP3") (pin "1") (pinfunction "1_1") (pintype "passive"))
      (node (ref "TP22") (pin "P$1") (pinfunction "TP_P$1") (pintype "input"))
      (node (ref "VR2") (pin "E") (pinfunction "E_E") (pintype "passive"))
    )
    (net (code "55") (name "Net-(U1-COMP)") (class "Default")
      (node (ref "CC1") (pin "1") (pinfunction "1_1") (pintype "passive"))
      (node (ref "CC2") (pin "1") (pinfunction "1_1") (pintype "passive"))
      (node (ref "U1") (pin "P1") (pinfunction "COMP_P1") (pintype "bidirectional"))
    )
    (net (code "56") (name "Net-(U1-EN)") (class "Default")
      (node (ref "REN") (pin "1") (pinfunction "1_1") (pintype "passive"))
      (node (ref "U1") (pin "P3") (pinfunction "EN_P3") (pintype "bidirectional"))
    )
    (net (code "57") (name "Net-(U1-FB)") (class "Default")
      (node (ref "RF1") (pin "1") (pinfunction "1_1") (pintype "passive"))
      (node (ref "RF2") (pin "2") (pinfunction "2_2") (pintype "passive"))
      (node (ref "U1") (pin "P2") (pinfunction "FB_P2") (pintype "bidirectional"))
    )
    (net (code "58") (name "Net-(U1-SS)") (class "Default")
      (node (ref "CSS") (pin "1") (pinfunction "1_1") (pintype "passive"))
      (node (ref "U1") (pin "P8") (pinfunction "SS_P8") (pintype "bidirectional"))
    )
    (net (code "59") (name "Net-(U1-VIN)") (class "Default")
      (node (ref "CV5") (pin "1") (pinfunction "1_1") (pintype "passive"))
      (node (ref "RB0") (pin "1") (pinfunction "1_1") (pintype "passive"))
      (node (ref "REN") (pin "2") (pinfunction "2_2") (pintype "passive"))
      (node (ref "U1") (pin "P6") (pinfunction "VIN_P6") (pintype "bidirectional"))
    )
    (net (code "60") (name "Net-(U2-BST)") (class "Default")
      (node (ref "CBST-NEG") (pin "1") (pinfunction "1_1") (pintype "passive"))
      (node (ref "U2") (pin "1") (pinfunction "BST_1") (pintype "bidirectional"))
    )
    (net (code "61") (name "Net-(U2-FB)") (class "Default")
      (node (ref "RF1-NEG") (pin "1") (pinfunction "1_1") (pintype "passive"))
      (node (ref "RF2-NEG") (pin "1") (pinfunction "1_1") (pintype "passive"))
      (node (ref "U2") (pin "3") (pinfunction "FB_3") (pintype "input"))
    )
    (net (code "62") (name "Net-(VR3-E)") (class "Default")
      (node (ref "VR3") (pin "P$3") (pinfunction "E_P$3") (pintype "passive"))
      (node (ref "X2") (pin "2") (pinfunction "2_2") (pintype "passive"))
    )
    (net (code "63") (name "Net-(VR4-E)") (class "Default")
      (node (ref "VR4") (pin "P$3") (pinfunction "E_P$3") (pintype "passive"))
      (node (ref "X3") (pin "2") (pinfunction "2_2") (pintype "passive"))
    )
    (net (code "64") (name "Net-(VR5-E)") (class "Default")
      (node (ref "R16") (pin "1") (pinfunction "1_1") (pintype "passive"))
      (node (ref "VR5") (pin "P$2") (pinfunction "S_P$2") (pintype "passive"))
      (node (ref "VR5") (pin "P$3") (pinfunction "E_P$3") (pintype "passive"))
    )
    (net (code "65") (name "TOMIC") (class "Default")
      (node (ref "CON2") (pin "P$2") (pinfunction "3_P$2") (pintype "passive"))
      (node (ref "R29") (pin "1") (pinfunction "1_1") (pintype "passive"))
      (node (ref "R33") (pin "2") (pinfunction "2_2") (pintype "passive"))
    )
    (net (code "66") (name "TP5") (class "Default")
      (node (ref "IC1") (pin "8") (pinfunction "OUT_8") (pintype "output"))
      (node (ref "IC2") (pin "2") (pinfunction "-IN_2") (pintype "input"))
      (node (ref "R24") (pin "2") (pinfunction "2_2") (pintype "passive"))
      (node (ref "TP5") (pin "P$1") (pinfunction "TP_P$1") (pintype "input"))
      (node (ref "X2") (pin "1") (pinfunction "1_1") (pintype "passive"))
    )
    (net (code "67") (name "TP6") (class "Default")
      (node (ref "IC1") (pin "7") (pinfunction "OUT_7") (pintype "output"))
      (node (ref "IC2") (pin "6") (pinfunction "-IN_6") (pintype "input"))
      (node (ref "R25") (pin "2") (pinfunction "2_2") (pintype "passive"))
      (node (ref "TP6") (pin "P$1") (pinfunction "TP_P$1") (pintype "input"))
      (node (ref "X3") (pin "1") (pinfunction "1_1") (pintype "passive"))
    )
    (net (code "68") (name "USB5V") (class "Default")
      (node (ref "CC-NEG") (pin "1") (pinfunction "1_1") (pintype "passive"))
      (node (ref "CIN") (pin "1") (pinfunction "1_1") (pintype "passive"))
      (node (ref "CIN-NEG") (pin "1") (pinfunction "1_1") (pintype "passive"))
      (node (ref "L1") (pin "1") (pinfunction "1_1") (pintype "passive"))
      (node (ref "RB0") (pin "2") (pinfunction "2_2") (pintype "passive"))
      (node (ref "TP7") (pin "P$1") (pinfunction "TP_P$1") (pintype "input"))
      (node (ref "U2") (pin "4") (pinfunction "EN_4") (pintype "input"))
      (node (ref "U2") (pin "5") (pinfunction "VIN_5") (pintype "power_in"))
      (node (ref "USB2") (pin "P$1") (pinfunction "1_P$1") (pintype "input"))
    )
    (net (code "69") (name "V+") (class "Default")
      (node (ref "COUT1") (pin "1") (pinfunction "1_1") (pintype "passive"))
      (node (ref "D3") (pin "C") (pinfunction "C_C") (pintype "passive"))
      (node (ref "IC1") (pin "4") (pinfunction "V+_4") (pintype "power_in"))
      (node (ref "IC2") (pin "4") (pinfunction "V+_4") (pintype "power_in"))
      (node (ref "IC3") (pin "4") (pinfunction "V+_4") (pintype "power_in"))
      (node (ref "IC4") (pin "2") (pinfunction "V+_2") (pintype "power_in"))
      (node (ref "IC5") (pin "2") (pinfunction "V+_2") (pintype "power_in"))
      (node (ref "R15") (pin "2") (pinfunction "2_2") (pintype "passive"))
      (node (ref "R16") (pin "2") (pinfunction "2_2") (pintype "passive"))
      (node (ref "R23") (pin "2") (pinfunction "2_2") (pintype "passive"))
      (node (ref "RF1") (pin "2") (pinfunction "2_2") (pintype "passive"))
      (node (ref "TP10") (pin "P$1") (pinfunction "TP_P$1") (pintype "input"))
      (node (ref "X7") (pin "3") (pinfunction "1_3") (pintype "passive"))
      (node (ref "X9") (pin "1") (pinfunction "1_1") (pintype "passive"))
    )
    (net (code "70") (name "V-") (class "Default")
      (node (ref "CC-NEG") (pin "2") (pinfunction "2_2") (pintype "passive"))
      (node (ref "COUT1-NEG") (pin "2") (pinfunction "2_2") (pintype "passive"))
      (node (ref "D1-NEG") (pin "A") (pinfunction "A_A") (pintype "passive"))
      (node (ref "IC1") (pin "11") (pinfunction "V-_11") (pintype "power_in"))
      (node (ref "IC2") (pin "11") (pinfunction "V-_11") (pintype "power_in"))
      (node (ref "IC3") (pin "11") (pinfunction "V-_11") (pintype "power_in"))
      (node (ref "IC4") (pin "5") (pinfunction "V-_5") (pintype "power_in"))
      (node (ref "IC5") (pin "5") (pinfunction "V-_5") (pintype "power_in"))
      (node (ref "RF2-NEG") (pin "2") (pinfunction "2_2") (pintype "passive"))
      (node (ref "TP11") (pin "P$1") (pinfunction "TP_P$1") (pintype "input"))
      (node (ref "U2") (pin "2") (pinfunction "AGND_2") (pintype "power_in"))
      (node (ref "X9") (pin "3") (pinfunction "1_3") (pintype "passive"))
    )
    (net (code "71") (name "unconnected-(CON2-2-PadP$3)") (class "Default")
      (node (ref "CON2") (pin "P$3") (pinfunction "2_P$3") (pintype "passive"))
    )
    (net (code "72") (name "unconnected-(USB2A-2-PadP$2)") (class "Default")
      (node (ref "USB2") (pin "P$2") (pinfunction "2_P$2") (pintype "input"))
    )
    (net (code "73") (name "unconnected-(USB2A-3-PadP$3)") (class "Default")
      (node (ref "USB2") (pin "P$3") (pinfunction "3_P$3") (pintype "input"))
    )
    (net (code "74") (name "unconnected-(USB2A-4-PadP$4)") (class "Default")
      (node (ref "USB2") (pin "P$4") (pinfunction "4_P$4") (pintype "input"))
    )
  )
)
